# LCD_8bit.net
KiCad netlist of a schematic drawn in EAGLE
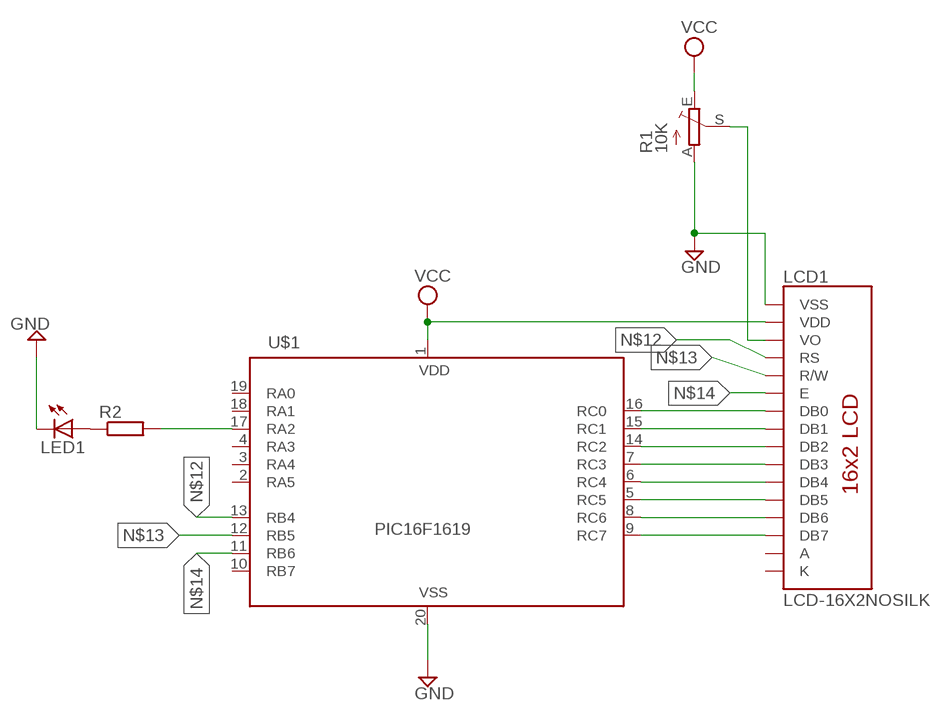
[diagram p0: schematic, sheet 1]

(export (version "E")
  (design (tool "Eeschema 10.0.6"))
  (components
    (comp (ref "LCD1")
      (value "LCD-16X2NOSILK")
      (footprint "eagle-import:LCD-16X2_NOSILK")
      (libsource (lib "eagle-import") (part "LCD-16X2NOSILK"))
    )
    (comp (ref "LED1")
      (value "LEDB155")
      (footprint "eagle-import:Q62902-B155")
      (libsource (lib "eagle-import") (part "LEDB155"))
    )
    (comp (ref "R1")
      (value "10K")
      (footprint "eagle-import:B25P")
      (libsource (lib "eagle-import") (part "TRIM_EU-B25P"))
    )
    (comp (ref "R2")
      (value "R-EU_0309/V")
      (footprint "eagle-import:0309V")
      (libsource (lib "eagle-import") (part "R-EU_0309/V"))
    )
    (comp (ref "U$1")
      (value "PIC16F1619")
      (footprint "eagle-import:DIP20B")
      (libsource (lib "eagle-import") (part "PIC16F1619-DIP"))
    )
  )
  (nets
    (net (code "1") (name "/A") (class "Default")
      (node (ref "LCD1") (pin "15") (pinfunction "A_15") (pintype "power_in"))
    )
    (net (code "2") (name "/K") (class "Default")
      (node (ref "LCD1") (pin "16") (pinfunction "K_16") (pintype "power_in"))
    )
    (net (code "3") (name "GND") (class "Default")
      (node (ref "LCD1") (pin "1") (pinfunction "VSS_1") (pintype "power_in"))
      (node (ref "LED1") (pin "K") (pinfunction "C_K") (pintype "passive"))
      (node (ref "R1") (pin "A") (pinfunction "A_A") (pintype "passive"))
      (node (ref "U$1") (pin "20") (pinfunction "VSS_20") (pintype "power_in"))
    )
    (net (code "4") (name "N$12") (class "Default")
      (node (ref "LCD1") (pin "4") (pinfunction "RS_4") (pintype "input"))
      (node (ref "U$1") (pin "13") (pinfunction "RB4_13") (pintype "bidirectional"))
    )
    (net (code "5") (name "N$13") (class "Default")
      (node (ref "LCD1") (pin "5") (pinfunction "R/W_5") (pintype "input"))
      (node (ref "U$1") (pin "12") (pinfunction "RB5_12") (pintype "bidirectional"))
    )
    (net (code "6") (name "N$14") (class "Default")
      (node (ref "LCD1") (pin "6") (pinfunction "E_6") (pintype "input"))
      (node (ref "U$1") (pin "11") (pinfunction "RB6_11") (pintype "bidirectional"))
    )
    (net (code "7") (name "Net-(LCD1-DB0)") (class "Default")
      (node (ref "LCD1") (pin "7") (pinfunction "DB0_7") (pintype "bidirectional"))
      (node (ref "U$1") (pin "16") (pinfunction "RC0_16") (pintype "bidirectional"))
    )
    (net (code "8") (name "Net-(LCD1-DB1)") (class "Default")
      (node (ref "LCD1") (pin "8") (pinfunction "DB1_8") (pintype "bidirectional"))
      (node (ref "U$1") (pin "15") (pinfunction "RC1_15") (pintype "bidirectional"))
    )
    (net (code "9") (name "Net-(LCD1-DB2)") (class "Default")
      (node (ref "LCD1") (pin "9") (pinfunction "DB2_9") (pintype "bidirectional"))
      (node (ref "U$1") (pin "14") (pinfunction "RC2_14") (pintype "bidirectional"))
    )
    (net (code "10") (name "Net-(LCD1-DB3)") (class "Default")
      (node (ref "LCD1") (pin "10") (pinfunction "DB3_10") (pintype "bidirectional"))
      (node (ref "U$1") (pin "7") (pinfunction "RC3_7") (pintype "bidirectional"))
    )
    (net (code "11") (name "Net-(LCD1-DB4)") (class "Default")
      (node (ref "LCD1") (pin "11") (pinfunction "DB4_11") (pintype "bidirectional"))
      (node (ref "U$1") (pin "6") (pinfunction "RC4_6") (pintype "bidirectional"))
    )
    (net (code "12") (name "Net-(LCD1-DB5)") (class "Default")
      (node (ref "LCD1") (pin "12") (pinfunction "DB5_12") (pintype "bidirectional"))
      (node (ref "U$1") (pin "5") (pinfunction "RC5_5") (pintype "bidirectional"))
    )
    (net (code "13") (name "Net-(LCD1-DB6)") (class "Default")
      (node (ref "LCD1") (pin "13") (pinfunction "DB6_13") (pintype "bidirectional"))
      (node (ref "U$1") (pin "8") (pinfunction "RC6_8") (pintype "bidirectional"))
    )
    (net (code "14") (name "Net-(LCD1-DB7)") (class "Default")
      (node (ref "LCD1") (pin "14") (pinfunction "DB7_14") (pintype "bidirectional"))
      (node (ref "U$1") (pin "9") (pinfunction "RC7_9") (pintype "bidirectional"))
    )
    (net (code "15") (name "Net-(LCD1-VO)") (class "Default")
      (node (ref "LCD1") (pin "3") (pinfunction "VO_3") (pintype "bidirectional"))
      (node (ref "R1") (pin "S") (pinfunction "S_S") (pintype "passive"))
    )
    (net (code "16") (name "Net-(LED1-PadA)") (class "Default")
      (node (ref "LED1") (pin "A") (pinfunction "A_A") (pintype "passive"))
      (node (ref "R2") (pin "1") (pinfunction "1_1") (pintype "passive"))
    )
    (net (code "17") (name "Net-(U$1-RA2)") (class "Default")
      (node (ref "R2") (pin "2") (pinfunction "2_2") (pintype "passive"))
      (node (ref "U$1") (pin "17") (pinfunction "RA2_17") (pintype "bidirectional"))
    )
    (net (code "18") (name "VCC") (class "Default")
      (node (ref "LCD1") (pin "2") (pinfunction "VDD_2") (pintype "power_in"))
      (node (ref "R1") (pin "E") (pinfunction "E_E") (pintype "passive"))
      (node (ref "U$1") (pin "1") (pinfunction "VDD_1") (pintype "power_in"))
    )
    (net (code "19") (name "unconnected-(U$1-RA0-Pad19)") (class "Default")
      (node (ref "U$1") (pin "19") (pinfunction "RA0_19") (pintype "bidirectional"))
    )
    (net (code "20") (name "unconnected-(U$1-RA1-Pad18)") (class "Default")
      (node (ref "U$1") (pin "18") (pinfunction "RA1_18") (pintype "bidirectional"))
    )
    (net (code "21") (name "unconnected-(U$1-RA3-Pad4)") (class "Default")
      (node (ref "U$1") (pin "4") (pinfunction "RA3_4") (pintype "input"))
    )
    (net (code "22") (name "unconnected-(U$1-RA4-Pad3)") (class "Default")
      (node (ref "U$1") (pin "3") (pinfunction "RA4_3") (pintype "bidirectional"))
    )
    (net (code "23") (name "unconnected-(U$1-RA5-Pad2)") (class "Default")
      (node (ref "U$1") (pin "2") (pinfunction "RA5_2") (pintype "bidirectional"))
    )
    (net (code "24") (name "unconnected-(U$1-RB7-Pad10)") (class "Default")
      (node (ref "U$1") (pin "10") (pinfunction "RB7_10") (pintype "bidirectional"))
    )
  )
)
